# Servo_tester_rev1.net
KiCad netlist of a schematic drawn in EAGLE
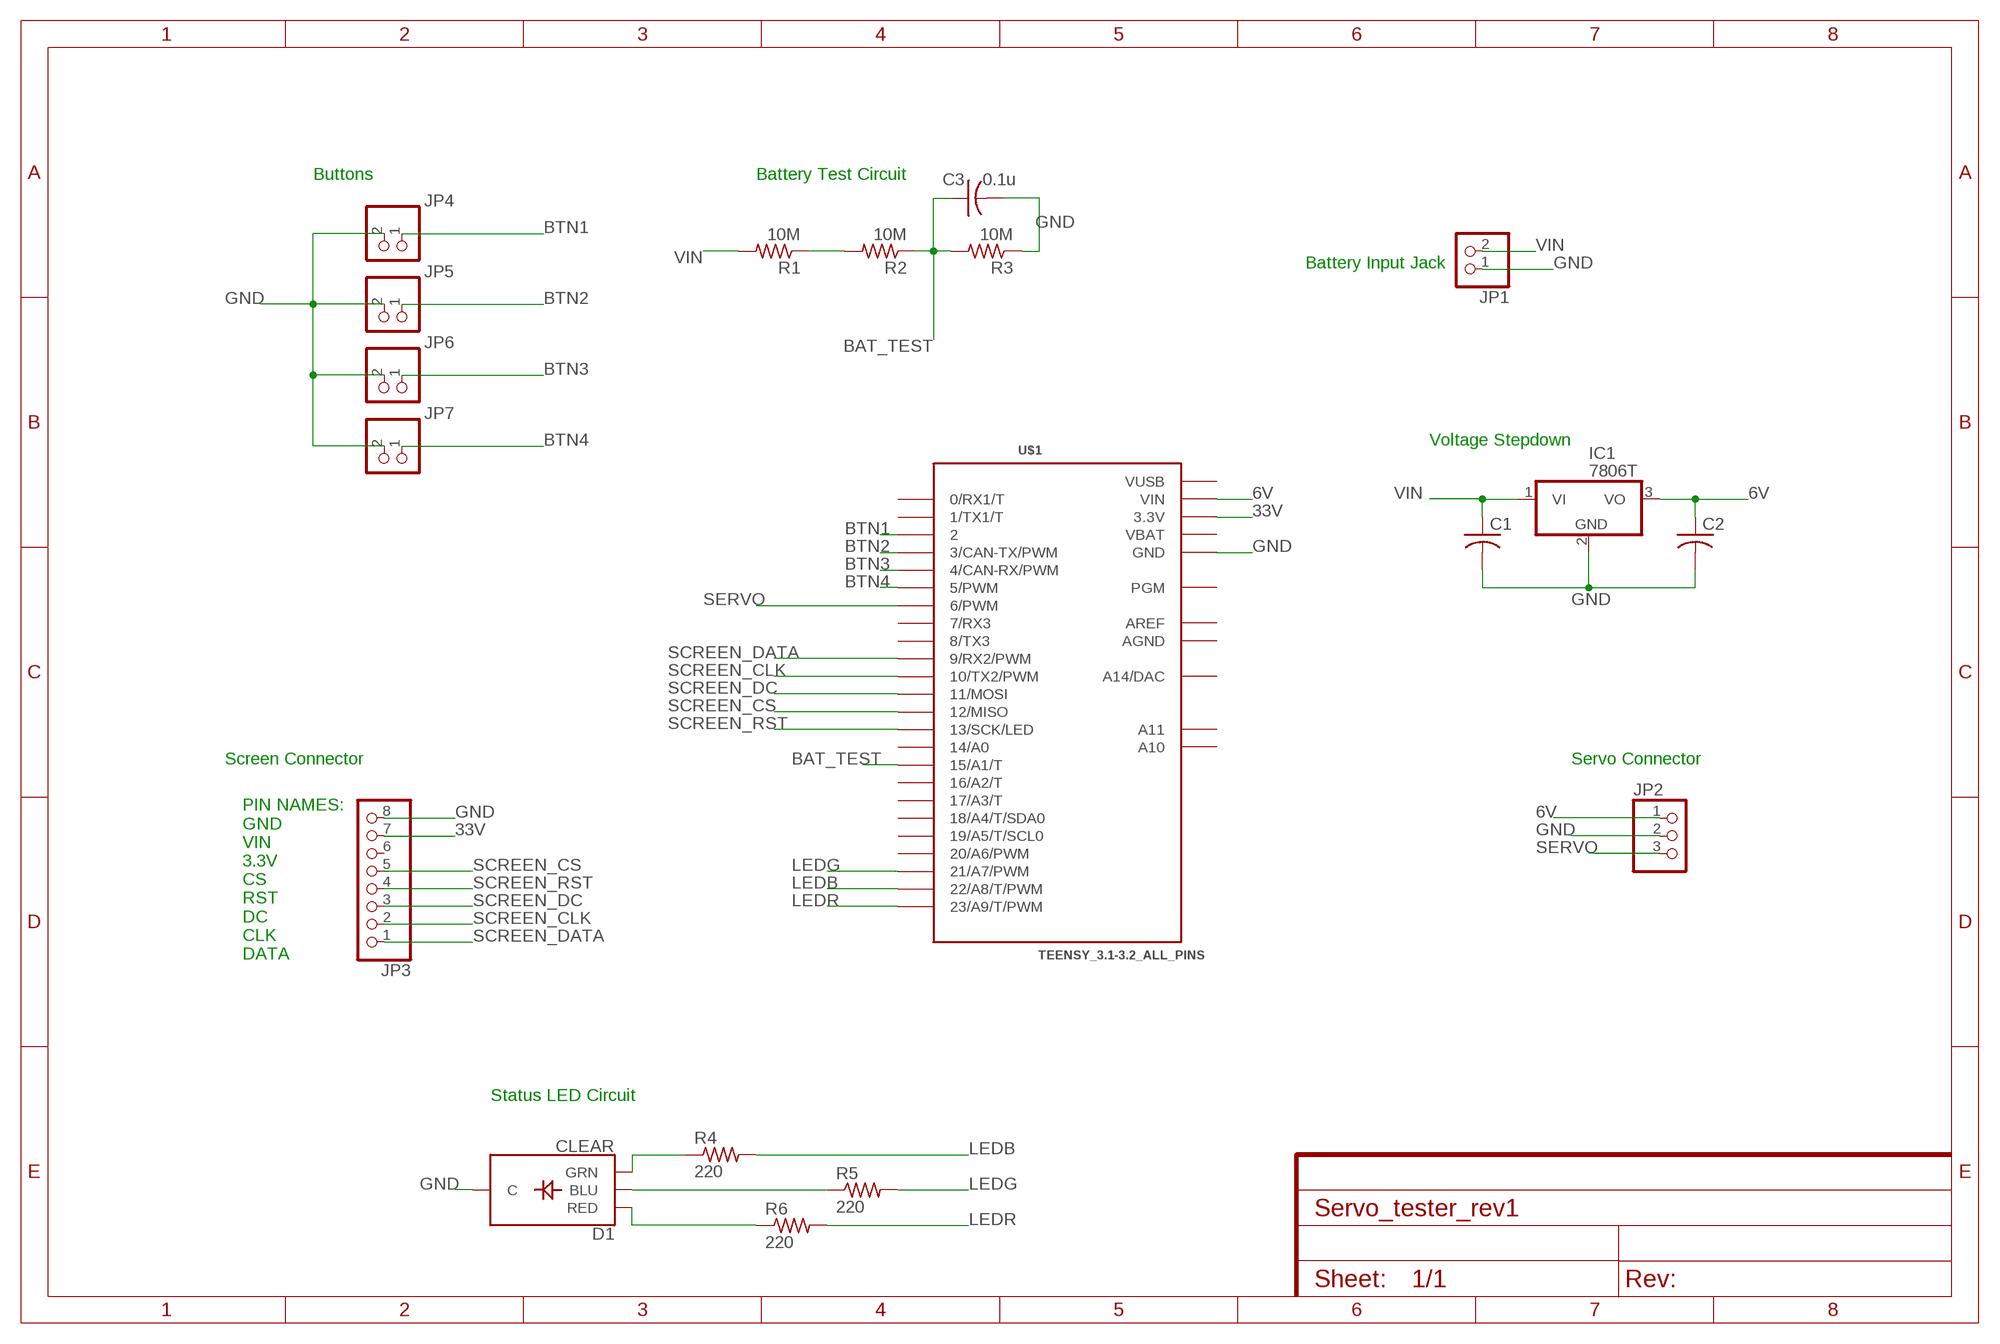
[diagram p0: schematic, sheet 1]

(export (version "E")
  (design (tool "Eeschema 10.0.6"))
  (components
    (comp (ref "C1")
      (value "C-US050-024X044")
      (footprint "eagle-import:C050-024X044")
      (libsource (lib "eagle-import") (part "C-US050-024X044"))
    )
    (comp (ref "C2")
      (value "C-US050-024X044")
      (footprint "eagle-import:C050-024X044")
      (libsource (lib "eagle-import") (part "C-US050-024X044"))
    )
    (comp (ref "C3")
      (value "0.1u")
      (footprint "eagle-import:C050-024X044")
      (libsource (lib "eagle-import") (part "C-US050-024X044"))
    )
    (comp (ref "D1")
      (value "CLEAR")
      (footprint "eagle-import:LED-RGB-THRU")
      (libsource (lib "eagle-import") (part "LED-RGB-CCCLEAR"))
    )
    (comp (ref "IC1")
      (value "7806T")
      (footprint "eagle-import:TO220H")
      (libsource (lib "eagle-import") (part "78T06"))
    )
    (comp (ref "JP1")
      (value "HEADER-1X2ROUND")
      (footprint "eagle-import:1X02_ROUND")
      (libsource (lib "eagle-import") (part "HEADER-1X2ROUND"))
    )
    (comp (ref "JP2")
      (value "HEADER-1X3ROUND")
      (footprint "eagle-import:1X03_ROUND")
      (libsource (lib "eagle-import") (part "HEADER-1X3ROUND"))
    )
    (comp (ref "JP3")
      (value "HEADER-1X870MIL")
      (footprint "eagle-import:1X08_ROUND_70")
      (libsource (lib "eagle-import") (part "HEADER-1X870MIL"))
    )
    (comp (ref "JP4")
      (value "HEADER-1X2ROUND")
      (footprint "eagle-import:1X02_ROUND")
      (libsource (lib "eagle-import") (part "HEADER-1X2ROUND"))
    )
    (comp (ref "JP5")
      (value "HEADER-1X2ROUND")
      (footprint "eagle-import:1X02_ROUND")
      (libsource (lib "eagle-import") (part "HEADER-1X2ROUND"))
    )
    (comp (ref "JP6")
      (value "HEADER-1X2ROUND")
      (footprint "eagle-import:1X02_ROUND")
      (libsource (lib "eagle-import") (part "HEADER-1X2ROUND"))
    )
    (comp (ref "JP7")
      (value "HEADER-1X2ROUND")
      (footprint "eagle-import:1X02_ROUND")
      (libsource (lib "eagle-import") (part "HEADER-1X2ROUND"))
    )
    (comp (ref "R1")
      (value "10M")
      (footprint "eagle-import:0204_5")
      (libsource (lib "eagle-import") (part "R-US_0204/5"))
    )
    (comp (ref "R2")
      (value "10M")
      (footprint "eagle-import:0204_5")
      (libsource (lib "eagle-import") (part "R-US_0204/5"))
    )
    (comp (ref "R3")
      (value "10M")
      (footprint "eagle-import:0204_5")
      (libsource (lib "eagle-import") (part "R-US_0204/5"))
    )
    (comp (ref "R4")
      (value "220")
      (footprint "eagle-import:0204_5")
      (libsource (lib "eagle-import") (part "R-US_0204/5"))
    )
    (comp (ref "R5")
      (value "220")
      (footprint "eagle-import:0204_5")
      (libsource (lib "eagle-import") (part "R-US_0204/5"))
    )
    (comp (ref "R6")
      (value "220")
      (footprint "eagle-import:0204_5")
      (libsource (lib "eagle-import") (part "R-US_0204/5"))
    )
    (comp (ref "U$1")
      (value "TEENSY_3.1-3.2_ALL_PINS")
      (footprint "eagle-import:TEENSY_3.0-3.2&LC_ALL_PINS")
      (libsource (lib "eagle-import") (part "TEENSY_3.1-3.2_ALL_PINS"))
    )
  )
  (nets
    (net (code "1") (name "/6V") (class "Default")
      (node (ref "C2") (pin "1") (pinfunction "1_1") (pintype "passive"))
      (node (ref "IC1") (pin "3") (pinfunction "VO_3") (pintype "passive"))
      (node (ref "JP2") (pin "1") (pinfunction "1_1") (pintype "passive"))
      (node (ref "U$1") (pin "VIN") (pinfunction "VIN_VIN") (pintype "power_in"))
    )
    (net (code "2") (name "/33V") (class "Default")
      (node (ref "JP3") (pin "7") (pinfunction "7_7") (pintype "passive"))
      (node (ref "U$1") (pin "3.3V") (pinfunction "3.3V_3.3V") (pintype "power_in"))
      (node (ref "U$1") (pin "3.3V1") (pinfunction "3.3V_3.3V1") (pintype "power_in"))
    )
    (net (code "3") (name "/AGND") (class "Default")
      (node (ref "U$1") (pin "AGND") (pinfunction "AGND_AGND") (pintype "power_in"))
    )
    (net (code "4") (name "/AREF") (class "Default")
      (node (ref "U$1") (pin "AREF") (pinfunction "AREF_AREF") (pintype "power_in"))
    )
    (net (code "5") (name "/BAT_TEST") (class "Default")
      (node (ref "C3") (pin "1") (pinfunction "1_1") (pintype "passive"))
      (node (ref "R2") (pin "1") (pinfunction "1_1") (pintype "passive"))
      (node (ref "R3") (pin "2") (pinfunction "2_2") (pintype "passive"))
      (node (ref "U$1") (pin "15/A1") (pinfunction "15/A1/T_15/A1") (pintype "bidirectional"))
    )
    (net (code "6") (name "/BTN1") (class "Default")
      (node (ref "JP4") (pin "1") (pinfunction "1_1") (pintype "passive"))
      (node (ref "U$1") (pin "2") (pinfunction "2_2") (pintype "bidirectional"))
    )
    (net (code "7") (name "/BTN2") (class "Default")
      (node (ref "JP5") (pin "1") (pinfunction "1_1") (pintype "passive"))
      (node (ref "U$1") (pin "3") (pinfunction "3/CAN-TX/PWM_3") (pintype "bidirectional"))
    )
    (net (code "8") (name "/BTN3") (class "Default")
      (node (ref "JP6") (pin "1") (pinfunction "1_1") (pintype "passive"))
      (node (ref "U$1") (pin "4") (pinfunction "4/CAN-RX/PWM_4") (pintype "bidirectional"))
    )
    (net (code "9") (name "/BTN4") (class "Default")
      (node (ref "JP7") (pin "1") (pinfunction "1_1") (pintype "passive"))
      (node (ref "U$1") (pin "5") (pinfunction "5/PWM_5") (pintype "bidirectional"))
    )
    (net (code "10") (name "/GND") (class "Default")
      (node (ref "C1") (pin "2") (pinfunction "2_2") (pintype "passive"))
      (node (ref "C2") (pin "2") (pinfunction "2_2") (pintype "passive"))
      (node (ref "C3") (pin "2") (pinfunction "2_2") (pintype "passive"))
      (node (ref "D1") (pin "2") (pinfunction "C_2") (pintype "bidirectional"))
      (node (ref "IC1") (pin "2") (pinfunction "GND_2") (pintype "passive"))
      (node (ref "JP1") (pin "1") (pinfunction "1_1") (pintype "passive"))
      (node (ref "JP2") (pin "2") (pinfunction "2_2") (pintype "passive"))
      (node (ref "JP3") (pin "8") (pinfunction "8_8") (pintype "passive"))
      (node (ref "JP4") (pin "2") (pinfunction "2_2") (pintype "passive"))
      (node (ref "JP5") (pin "2") (pinfunction "2_2") (pintype "passive"))
      (node (ref "JP6") (pin "2") (pinfunction "2_2") (pintype "passive"))
      (node (ref "JP7") (pin "2") (pinfunction "2_2") (pintype "passive"))
      (node (ref "R3") (pin "1") (pinfunction "1_1") (pintype "passive"))
      (node (ref "U$1") (pin "GND") (pinfunction "GND_GND") (pintype "power_in"))
      (node (ref "U$1") (pin "GND1") (pinfunction "GND_GND1") (pintype "power_in"))
    )
    (net (code "11") (name "/LEDB") (class "Default")
      (node (ref "R4") (pin "2") (pinfunction "2_2") (pintype "passive"))
      (node (ref "U$1") (pin "22/A8") (pinfunction "22/A8/T/PWM_22/A8") (pintype "bidirectional"))
    )
    (net (code "12") (name "/LEDG") (class "Default")
      (node (ref "R5") (pin "2") (pinfunction "2_2") (pintype "passive"))
      (node (ref "U$1") (pin "21/A7") (pinfunction "21/A7/PWM_21/A7") (pintype "bidirectional"))
    )
    (net (code "13") (name "/LEDR") (class "Default")
      (node (ref "R6") (pin "2") (pinfunction "2_2") (pintype "passive"))
      (node (ref "U$1") (pin "23/A9") (pinfunction "23/A9/T/PWM_23/A9") (pintype "bidirectional"))
    )
    (net (code "14") (name "/SCREEN_CLK") (class "Default")
      (node (ref "JP3") (pin "2") (pinfunction "2_2") (pintype "passive"))
      (node (ref "U$1") (pin "10") (pinfunction "10/TX2/PWM_10") (pintype "bidirectional"))
    )
    (net (code "15") (name "/SCREEN_CS") (class "Default")
      (node (ref "JP3") (pin "5") (pinfunction "5_5") (pintype "passive"))
      (node (ref "U$1") (pin "12") (pinfunction "12/MISO_12") (pintype "bidirectional"))
    )
    (net (code "16") (name "/SCREEN_DATA") (class "Default")
      (node (ref "JP3") (pin "1") (pinfunction "1_1") (pintype "passive"))
      (node (ref "U$1") (pin "9") (pinfunction "9/RX2/PWM_9") (pintype "bidirectional"))
    )
    (net (code "17") (name "/SCREEN_DC") (class "Default")
      (node (ref "JP3") (pin "3") (pinfunction "3_3") (pintype "passive"))
      (node (ref "U$1") (pin "11") (pinfunction "11/MOSI_11") (pintype "bidirectional"))
    )
    (net (code "18") (name "/SCREEN_RST") (class "Default")
      (node (ref "JP3") (pin "4") (pinfunction "4_4") (pintype "passive"))
      (node (ref "U$1") (pin "13") (pinfunction "13/SCK/LED_13") (pintype "bidirectional"))
    )
    (net (code "19") (name "/SERVO") (class "Default")
      (node (ref "JP2") (pin "3") (pinfunction "3_3") (pintype "passive"))
      (node (ref "U$1") (pin "6") (pinfunction "6/PWM_6") (pintype "bidirectional"))
    )
    (net (code "20") (name "/VBAT") (class "Default")
      (node (ref "U$1") (pin "VBAT") (pinfunction "VBAT_VBAT") (pintype "power_in"))
    )
    (net (code "21") (name "/VIN") (class "Default")
      (node (ref "C1") (pin "1") (pinfunction "1_1") (pintype "passive"))
      (node (ref "IC1") (pin "1") (pinfunction "VI_1") (pintype "input"))
      (node (ref "JP1") (pin "2") (pinfunction "2_2") (pintype "passive"))
      (node (ref "R1") (pin "2") (pinfunction "2_2") (pintype "passive"))
    )
    (net (code "22") (name "/VUSB") (class "Default")
      (node (ref "U$1") (pin "VUSB") (pinfunction "VUSB_VUSB") (pintype "power_in"))
    )
    (net (code "23") (name "Net-(D1-BLU)") (class "Default")
      (node (ref "D1") (pin "4") (pinfunction "BLU_4") (pintype "bidirectional"))
      (node (ref "R5") (pin "1") (pinfunction "1_1") (pintype "passive"))
    )
    (net (code "24") (name "Net-(D1-GRN)") (class "Default")
      (node (ref "D1") (pin "3") (pinfunction "GRN_3") (pintype "bidirectional"))
      (node (ref "R4") (pin "1") (pinfunction "1_1") (pintype "passive"))
    )
    (net (code "25") (name "Net-(D1-RED)") (class "Default")
      (node (ref "D1") (pin "1") (pinfunction "RED_1") (pintype "bidirectional"))
      (node (ref "R6") (pin "1") (pinfunction "1_1") (pintype "passive"))
    )
    (net (code "26") (name "Net-(R1-Pad1)") (class "Default")
      (node (ref "R1") (pin "1") (pinfunction "1_1") (pintype "passive"))
      (node (ref "R2") (pin "2") (pinfunction "2_2") (pintype "passive"))
    )
    (net (code "27") (name "unconnected-(JP3-Pad6)") (class "Default")
      (node (ref "JP3") (pin "6") (pinfunction "6_6") (pintype "passive"))
    )
    (net (code "28") (name "unconnected-(U$1-0{slash}RX1{slash}T-Pad0)") (class "Default")
      (node (ref "U$1") (pin "0") (pinfunction "0/RX1/T_0") (pintype "bidirectional"))
    )
    (net (code "29") (name "unconnected-(U$1-1{slash}TX1{slash}T-Pad1)") (class "Default")
      (node (ref "U$1") (pin "1") (pinfunction "1/TX1/T_1") (pintype "bidirectional"))
    )
    (net (code "30") (name "unconnected-(U$1-7{slash}RX3-Pad7)") (class "Default")
      (node (ref "U$1") (pin "7") (pinfunction "7/RX3_7") (pintype "bidirectional"))
    )
    (net (code "31") (name "unconnected-(U$1-8{slash}TX3-Pad8)") (class "Default")
      (node (ref "U$1") (pin "8") (pinfunction "8/TX3_8") (pintype "bidirectional"))
    )
    (net (code "32") (name "unconnected-(U$1-16{slash}A2{slash}T-Pad16{slash}A2)") (class "Default")
      (node (ref "U$1") (pin "16/A2") (pinfunction "16/A2/T_16/A2") (pintype "bidirectional"))
    )
    (net (code "33") (name "unconnected-(U$1-17{slash}A3{slash}T-Pad17{slash}A3)") (class "Default")
      (node (ref "U$1") (pin "17/A3") (pinfunction "17/A3/T_17/A3") (pintype "bidirectional"))
    )
    (net (code "34") (name "unconnected-(U$1-18{slash}A4{slash}T{slash}SDA0-Pad18{slash}A4)") (class "Default")
      (node (ref "U$1") (pin "18/A4") (pinfunction "18/A4/T/SDA0_18/A4") (pintype "bidirectional"))
    )
    (net (code "35") (name "unconnected-(U$1-19{slash}A5{slash}T{slash}SCL0-Pad19{slash}A5)") (class "Default")
      (node (ref "U$1") (pin "19/A5") (pinfunction "19/A5/T/SCL0_19/A5") (pintype "bidirectional"))
    )
    (net (code "36") (name "unconnected-(U$1-20{slash}A6{slash}PWM-Pad20{slash}A6)") (class "Default")
      (node (ref "U$1") (pin "20/A6") (pinfunction "20/A6/PWM_20/A6") (pintype "bidirectional"))
    )
    (net (code "37") (name "unconnected-(U$1-A14{slash}DAC-PadRESET{slash}DAC)") (class "Default")
      (node (ref "U$1") (pin "RESET/DAC") (pinfunction "A14/DAC_RESET/DAC") (pintype "bidirectional"))
    )
    (net (code "38") (name "unconnected-(U$1-Pad14{slash}A0)") (class "Default")
      (node (ref "U$1") (pin "14/A0") (pinfunction "14/A0_14/A0") (pintype "bidirectional"))
    )
    (net (code "39") (name "unconnected-(U$1-PadA10)") (class "Default")
      (node (ref "U$1") (pin "A10") (pinfunction "A10_A10") (pintype "bidirectional"))
    )
    (net (code "40") (name "unconnected-(U$1-PadA11)") (class "Default")
      (node (ref "U$1") (pin "A11") (pinfunction "A11_A11") (pintype "bidirectional"))
    )
    (net (code "41") (name "unconnected-(U$1-PadPGM)") (class "Default")
      (node (ref "U$1") (pin "PGM") (pinfunction "PGM_PGM") (pintype "bidirectional"))
    )
  )
)
